# BM22192DA06_SCH.net
KiCad netlist of a schematic drawn in Altium Designer
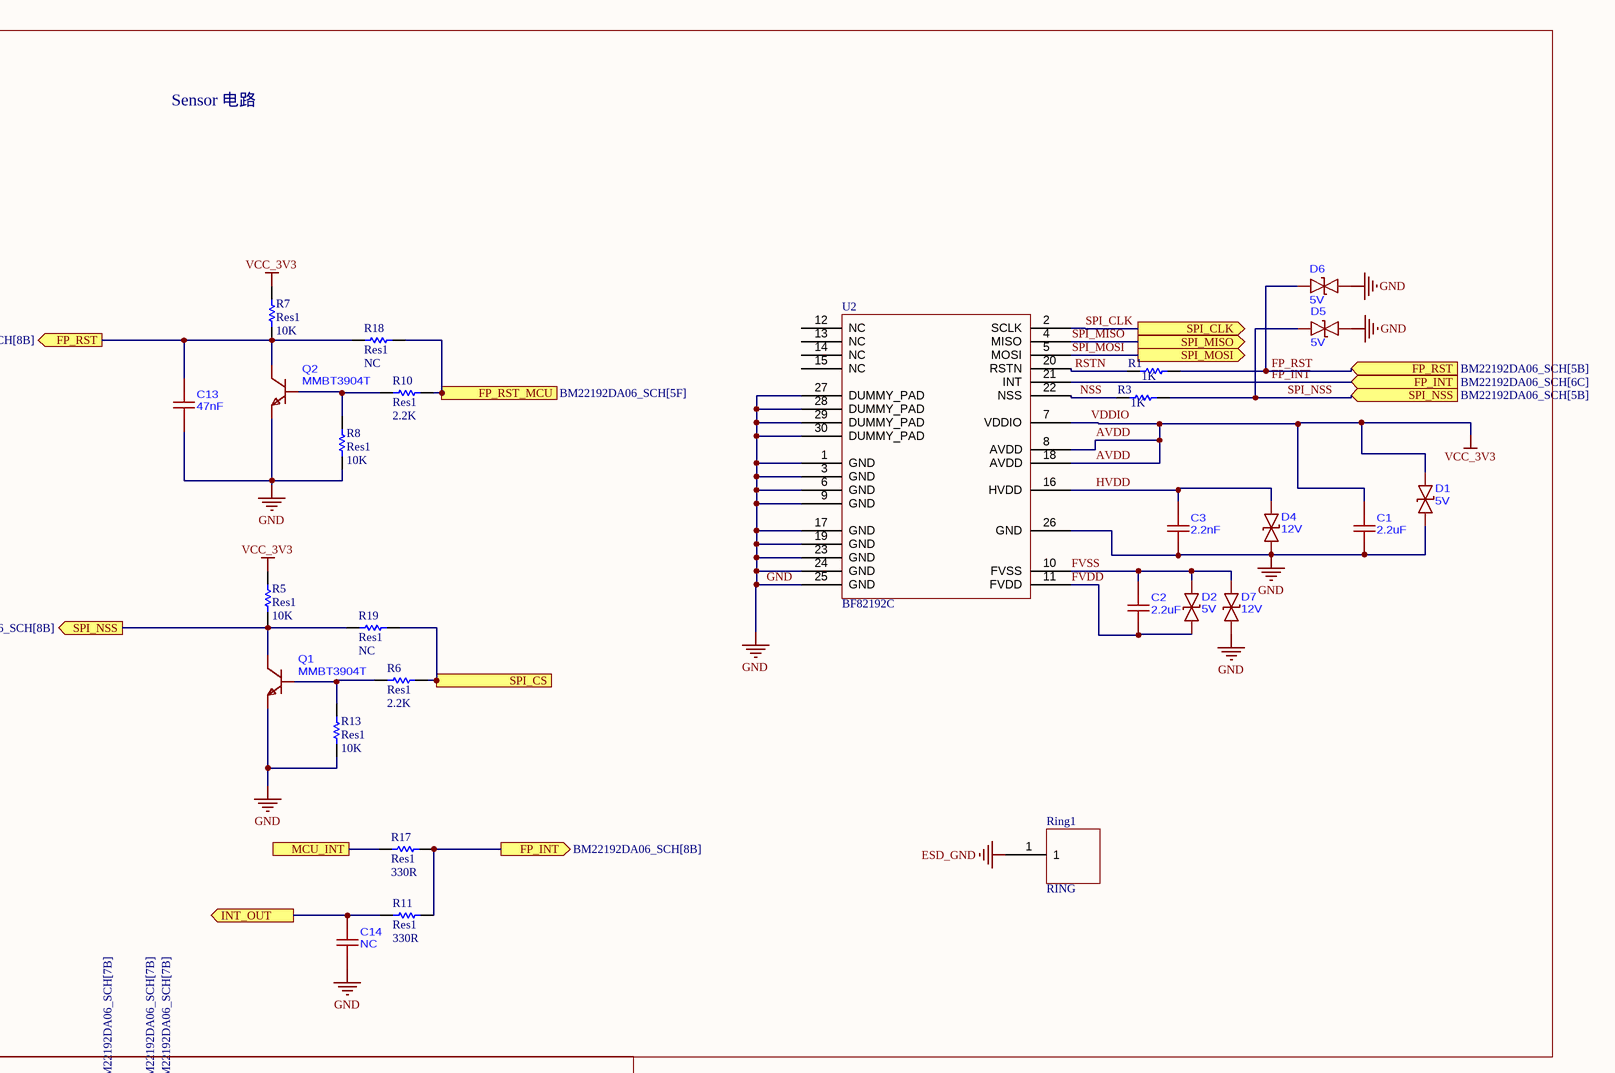
[diagram p0: BM22192DA06_SCH.SchDoc, top right]
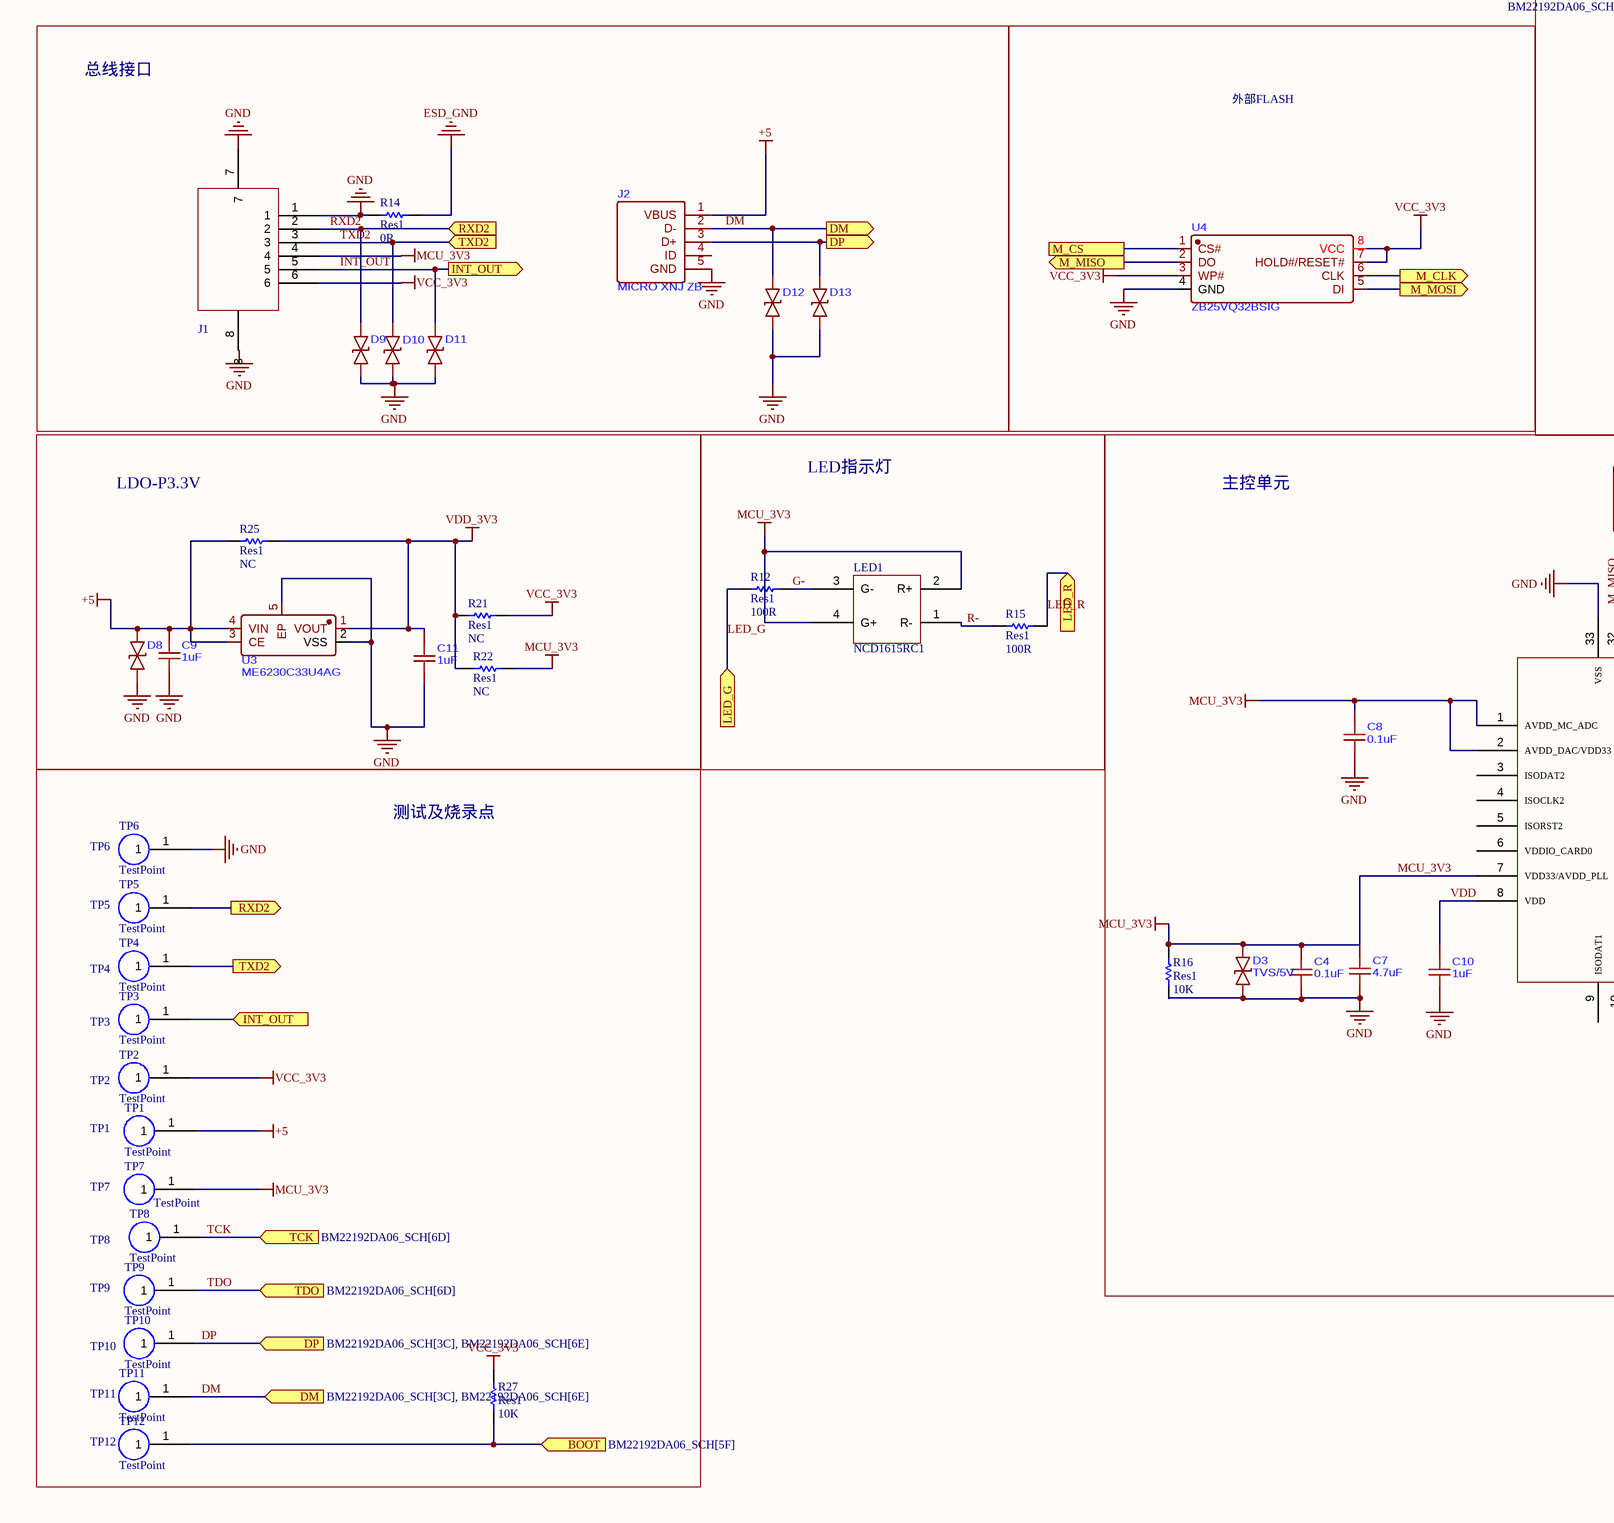
[diagram p1: BM22192DA06_SCH.SchDoc, bottom left]
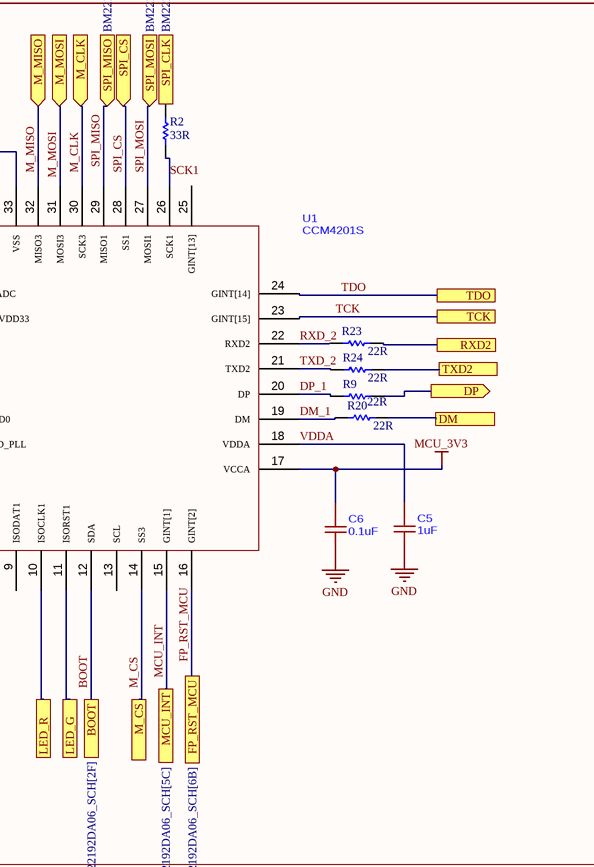
[diagram p2: BM22192DA06_SCH.SchDoc, bottom right]

(export (version "E")
  (design (tool "Eeschema 10.0.6"))
  (components
    (comp (ref "C1")
      (value "2.2uF")
      (footprint "C0201")
      (description "CAP")
      (libsource (lib "BLM") (part "C0201"))
    )
    (comp (ref "C2")
      (value "2.2uF")
      (footprint "C0201")
      (description "CAP")
      (libsource (lib "BLM") (part "C0201"))
    )
    (comp (ref "C3")
      (value "2.2nF")
      (footprint "C0201")
      (description "CAP")
      (libsource (lib "BLM") (part "C0201"))
    )
    (comp (ref "C4")
      (value "0.1uF")
      (footprint "C0201")
      (description "CAP")
      (libsource (lib "BLM") (part "C0201"))
    )
    (comp (ref "C5") (value "1uF") (footprint "C0402") (libsource (lib "BLM") (part "C0201")))
    (comp (ref "C6")
      (value "0.1uF")
      (footprint "C0201")
      (description "CAP")
      (libsource (lib "BLM") (part "C0201"))
    )
    (comp (ref "C7") (value "4.7uF") (footprint "C0402") (libsource (lib "BLM") (part "C0201")))
    (comp (ref "C8")
      (value "0.1uF")
      (footprint "C0201")
      (description "CAP")
      (libsource (lib "BLM") (part "C0201"))
    )
    (comp (ref "C9") (value "1uF") (footprint "C0402") (libsource (lib "BLM") (part "C0201")))
    (comp (ref "C10") (value "1uF") (footprint "C0402") (libsource (lib "BLM") (part "C0201")))
    (comp (ref "C11") (value "1uF") (footprint "C0402") (libsource (lib "BLM") (part "C0201")))
    (comp (ref "C13")
      (value "47nF")
      (footprint "C0201")
      (description "CAP")
      (libsource (lib "BLM") (part "C0201"))
    )
    (comp (ref "C14")
      (value "NC")
      (footprint "C0201")
      (description "CAP")
      (libsource (lib "BLM") (part "C0201"))
    )
    (comp (ref "D1")
      (value "5V")
      (footprint "D0201-BI_A")
      (description "TVS")
      (libsource (lib "BLM") (part "RSFK9D3NT"))
    )
    (comp (ref "D2")
      (value "5V")
      (footprint "D0201-BI_A")
      (description "TVS")
      (libsource (lib "BLM") (part "RSFK9D3NT"))
    )
    (comp (ref "D3")
      (value "TVS/5V")
      (footprint "D0201-BI_A")
      (description "TVS")
      (libsource (lib "BLM") (part "RSFK9D3NT"))
    )
    (comp (ref "D4")
      (value "12V")
      (footprint "D0201-BI_A")
      (description "TVS")
      (libsource (lib "BLM") (part "RSFK9D3NT"))
    )
    (comp (ref "D5")
      (value "5V")
      (footprint "D0201-BI_A")
      (description "TVS")
      (libsource (lib "BLM") (part "RSFK9D3NT"))
    )
    (comp (ref "D6")
      (value "5V")
      (footprint "D0201-BI_A")
      (description "TVS")
      (libsource (lib "BLM") (part "RSFK9D3NT"))
    )
    (comp (ref "D7")
      (value "12V")
      (footprint "D0201-BI_A")
      (description "TVS")
      (libsource (lib "BLM") (part "RSFK9D3NT"))
    )
    (comp (ref "D8")
      (value "RSFK9D3NT")
      (footprint "D0201-BI_A")
      (description "TVS")
      (libsource (lib "BLM") (part "RSFK9D3NT"))
    )
    (comp (ref "D9") (value "RSFK9D3NT") (footprint "D0201-BI_A") (libsource (lib "BLM") (part "RSFK9D3NT")))
    (comp (ref "D10") (value "RSFK9D3NT") (footprint "D0201-BI_A") (libsource (lib "BLM") (part "RSFK9D3NT")))
    (comp (ref "D11") (value "RSFK9D3NT") (footprint "D0201-BI_A") (libsource (lib "BLM") (part "RSFK9D3NT")))
    (comp (ref "D12") (value "RSFK9D3NT") (footprint "D0201-BI_A") (libsource (lib "BLM") (part "RSFK9D3NT")))
    (comp (ref "D13") (value "RSFK9D3NT") (footprint "D0201-BI_A") (libsource (lib "BLM") (part "RSFK9D3NT")))
    (comp (ref "J1")
      (value "SM06B-GHS-TB(LF)(SN)")
      (footprint "CONN_SM06B-GHS-TB_JST")
      (description "Description")
      (libsource (lib "BLM") (part "SM06B-GHS-TBLFSN"))
    )
    (comp (ref "J2")
      (value "MICRO XNJ ZB")
      (footprint "MICRO-USB-SMD_MICRO-XNJ-ZB")
      (libsource (lib "BLM") (part "MICRO XNJ ZB"))
    )
    (comp (ref "LED1")
      (value "NCD1615RC1")
      (footprint "LED-SMD_4P-L1.6-W1.5-TL-1")
      (description "LED")
      (libsource (lib "BLM") (part "NCD1615RC1"))
    )
    (comp (ref "Q1")
      (value "MMBT3904T")
      (footprint "SOT-523-3_L1.6-W0.8-P1.00-LS1.6-BR")
      (description "NPN triode")
      (libsource (lib "BLM") (part "MMBT3904T"))
    )
    (comp (ref "Q2")
      (value "MMBT3904T")
      (footprint "SOT-523-3_L1.6-W0.8-P1.00-LS1.6-BR")
      (description "NPN triode")
      (libsource (lib "BLM") (part "MMBT3904T"))
    )
    (comp (ref "R1")
      (value "1K")
      (footprint "R0201")
      (description "Resistor")
      (fields (field (name "Comment") "Res1") (field (name "PUBLISHER") "Altium Limited"))
      (libsource (lib "Miscellaneous Devices") (part "Res1"))
    )
    (comp (ref "R2")
      (value "33R")
      (footprint "R0201")
      (description "Resistor")
      (fields (field (name "Comment") "Res1") (field (name "PUBLISHER") "Altium Limited"))
      (libsource (lib "Miscellaneous Devices") (part "Res1"))
    )
    (comp (ref "R3")
      (value "1K")
      (footprint "R0201")
      (description "Resistor")
      (fields (field (name "Comment") "Res1") (field (name "PUBLISHER") "Altium Limited"))
      (libsource (lib "Miscellaneous Devices") (part "Res1"))
    )
    (comp (ref "R5")
      (value "Res1")
      (footprint "R0201")
      (description "Resistor")
      (fields (field (name "ALTIUM_VALUE") "10K") (field (name "PUBLISHER") "Altium Limited"))
      (libsource (lib "Miscellaneous Devices") (part "Res1"))
    )
    (comp (ref "R6")
      (value "Res1")
      (footprint "R0201")
      (description "Resistor")
      (fields (field (name "ALTIUM_VALUE") "2.2K") (field (name "PUBLISHER") "Altium Limited"))
      (libsource (lib "Miscellaneous Devices") (part "Res1"))
    )
    (comp (ref "R7")
      (value "Res1")
      (footprint "R0201")
      (description "Resistor")
      (fields (field (name "ALTIUM_VALUE") "10K") (field (name "PUBLISHER") "Altium Limited"))
      (libsource (lib "Miscellaneous Devices") (part "Res1"))
    )
    (comp (ref "R8")
      (value "Res1")
      (footprint "R0201")
      (description "Resistor")
      (fields (field (name "ALTIUM_VALUE") "10K") (field (name "PUBLISHER") "Altium Limited"))
      (libsource (lib "Miscellaneous Devices") (part "Res1"))
    )
    (comp (ref "R9")
      (value "22R")
      (footprint "R0201")
      (description "Resistor")
      (fields (field (name "Comment") "Res1") (field (name "PUBLISHER") "Altium Limited"))
      (libsource (lib "Miscellaneous Devices") (part "Res1"))
    )
    (comp (ref "R10")
      (value "Res1")
      (footprint "R0201")
      (description "Resistor")
      (fields (field (name "ALTIUM_VALUE") "2.2K") (field (name "PUBLISHER") "Altium Limited"))
      (libsource (lib "Miscellaneous Devices") (part "Res1"))
    )
    (comp (ref "R11")
      (value "Res1")
      (footprint "R0201")
      (description "Resistor")
      (fields (field (name "ALTIUM_VALUE") "330R") (field (name "PUBLISHER") "Altium Limited"))
      (libsource (lib "Miscellaneous Devices") (part "Res1"))
    )
    (comp (ref "R12")
      (value "Res1")
      (footprint "R0201")
      (description "Resistor")
      (fields (field (name "ALTIUM_VALUE") "100R") (field (name "PUBLISHER") "Altium Limited"))
      (libsource (lib "Miscellaneous Devices") (part "Res1"))
    )
    (comp (ref "R13")
      (value "Res1")
      (footprint "R0201")
      (description "Resistor")
      (fields (field (name "ALTIUM_VALUE") "10K") (field (name "PUBLISHER") "Altium Limited"))
      (libsource (lib "Miscellaneous Devices") (part "Res1"))
    )
    (comp (ref "R14")
      (value "Res1")
      (footprint "R0201")
      (description "Resistor")
      (fields (field (name "ALTIUM_VALUE") "0R") (field (name "PUBLISHER") "Altium Limited"))
      (libsource (lib "Miscellaneous Devices") (part "Res1"))
    )
    (comp (ref "R15")
      (value "Res1")
      (footprint "R0201")
      (description "Resistor")
      (fields (field (name "ALTIUM_VALUE") "100R") (field (name "PUBLISHER") "Altium Limited"))
      (libsource (lib "Miscellaneous Devices") (part "Res1"))
    )
    (comp (ref "R16")
      (value "Res1")
      (footprint "R0201")
      (description "Resistor")
      (fields (field (name "ALTIUM_VALUE") "10K") (field (name "PUBLISHER") "Altium Limited"))
      (libsource (lib "Miscellaneous Devices") (part "Res1"))
    )
    (comp (ref "R17")
      (value "Res1")
      (footprint "R0201")
      (description "Resistor")
      (fields (field (name "ALTIUM_VALUE") "330R") (field (name "PUBLISHER") "Altium Limited"))
      (libsource (lib "Miscellaneous Devices") (part "Res1"))
    )
    (comp (ref "R18")
      (value "Res1")
      (footprint "R0201")
      (description "Resistor")
      (fields (field (name "ALTIUM_VALUE") "NC") (field (name "PUBLISHER") "Altium Limited"))
      (libsource (lib "Miscellaneous Devices") (part "Res1"))
    )
    (comp (ref "R19")
      (value "Res1")
      (footprint "R0201")
      (description "Resistor")
      (fields (field (name "ALTIUM_VALUE") "NC") (field (name "PUBLISHER") "Altium Limited"))
      (libsource (lib "Miscellaneous Devices") (part "Res1"))
    )
    (comp (ref "R20")
      (value "22R")
      (footprint "R0201")
      (description "Resistor")
      (fields (field (name "Comment") "Res1") (field (name "PUBLISHER") "Altium Limited"))
      (libsource (lib "Miscellaneous Devices") (part "Res1"))
    )
    (comp (ref "R21")
      (value "Res1")
      (footprint "R0201")
      (description "Resistor")
      (fields (field (name "ALTIUM_VALUE") "NC") (field (name "PUBLISHER") "Altium Limited"))
      (libsource (lib "Miscellaneous Devices") (part "Res1"))
    )
    (comp (ref "R22")
      (value "Res1")
      (footprint "R0201")
      (description "Resistor")
      (fields (field (name "ALTIUM_VALUE") "NC") (field (name "PUBLISHER") "Altium Limited"))
      (libsource (lib "Miscellaneous Devices") (part "Res1"))
    )
    (comp (ref "R23")
      (value "22R")
      (footprint "R0201")
      (description "Resistor")
      (fields (field (name "Comment") "Res1") (field (name "PUBLISHER") "Altium Limited"))
      (libsource (lib "Miscellaneous Devices") (part "Res1"))
    )
    (comp (ref "R24")
      (value "22R")
      (footprint "R0201")
      (description "Resistor")
      (fields (field (name "Comment") "Res1") (field (name "PUBLISHER") "Altium Limited"))
      (libsource (lib "Miscellaneous Devices") (part "Res1"))
    )
    (comp (ref "R25")
      (value "Res1")
      (footprint "R0201")
      (description "Resistor")
      (fields (field (name "ALTIUM_VALUE") "NC") (field (name "PUBLISHER") "Altium Limited"))
      (libsource (lib "Miscellaneous Devices") (part "Res1"))
    )
    (comp (ref "R27")
      (value "Res1")
      (footprint "R0201")
      (description "Resistor")
      (fields (field (name "ALTIUM_VALUE") "10K") (field (name "PUBLISHER") "Altium Limited"))
      (libsource (lib "Miscellaneous Devices") (part "Res1"))
    )
    (comp (ref "Ring1")
      (value "RING")
      (footprint "金属环")
      (description "Metal Ring")
      (libsource (lib "BLM") (part "RING"))
    )
    (comp (ref "TP1") (value "TestPoint") (footprint "TestPoint") (libsource (lib "BLM") (part "TestPoint")))
    (comp (ref "TP2") (value "TestPoint") (footprint "TestPoint") (libsource (lib "BLM") (part "TestPoint")))
    (comp (ref "TP3") (value "TestPoint") (footprint "TestPoint") (libsource (lib "BLM") (part "TestPoint")))
    (comp (ref "TP4") (value "TestPoint") (footprint "TestPoint") (libsource (lib "BLM") (part "TestPoint")))
    (comp (ref "TP5") (value "TestPoint") (footprint "TestPoint") (libsource (lib "BLM") (part "TestPoint")))
    (comp (ref "TP6") (value "TestPoint") (footprint "TestPoint") (libsource (lib "BLM") (part "TestPoint")))
    (comp (ref "TP7") (value "TestPoint") (footprint "TestPoint") (libsource (lib "BLM") (part "TestPoint")))
    (comp (ref "TP8") (value "TestPoint") (footprint "TestPoint") (libsource (lib "BLM") (part "TestPoint")))
    (comp (ref "TP9") (value "TestPoint") (footprint "TestPoint") (libsource (lib "BLM") (part "TestPoint")))
    (comp (ref "TP10") (value "TestPoint") (footprint "TestPoint") (libsource (lib "BLM") (part "TestPoint")))
    (comp (ref "TP11") (value "TestPoint") (footprint "TestPoint") (libsource (lib "BLM") (part "TestPoint")))
    (comp (ref "TP12") (value "TestPoint") (footprint "TestPoint") (libsource (lib "BLM") (part "TestPoint")))
    (comp (ref "U1")
      (value "CCM4201S")
      (footprint "QFN40P400X400X85_HS-33N")
      (libsource (lib "BLM") (part "CCM4201S"))
    )
    (comp (ref "U2") (value "BF82192C") (footprint "BF82192c") (libsource (lib "BLM") (part "BF82192C")))
    (comp (ref "U3")
      (value "ME6230C33U4AG")
      (footprint "FBP4L_L1.0-W1.0-P0.65-BL-EP")
      (description "LDO")
      (libsource (lib "BLM") (part "ME6230C33U4AG"))
    )
    (comp (ref "U4")
      (value "ZB25VQ32BSIG")
      (footprint "SOIJ-8_L5.3-W5.3-P1.27-LS7.9-BL")
      (libsource (lib "BLM") (part "ZB25VQ32BSIG"))
    )
  )
  (nets
    (net (code "1") (name "+5") (class "Default")
      (node (ref "C9") (pin "2") (pinfunction "2_2") (pintype "passive"))
      (node (ref "D8") (pin "2") (pinfunction "A_2") (pintype "passive"))
      (node (ref "J2") (pin "1") (pinfunction "VBUS_1") (pintype "passive"))
      (node (ref "R25") (pin "1") (pinfunction "1_1") (pintype "passive"))
      (node (ref "TP1") (pin "1") (pinfunction "1_1") (pintype "passive"))
      (node (ref "U3") (pin "3") (pinfunction "CE_3") (pintype "passive"))
      (node (ref "U3") (pin "4") (pinfunction "VIN_4") (pintype "passive"))
    )
    (net (code "2") (name "/BOOT") (class "Default")
      (node (ref "R27") (pin "1") (pinfunction "1_1") (pintype "passive"))
      (node (ref "TP12") (pin "1") (pinfunction "1_1") (pintype "passive"))
      (node (ref "U1") (pin "12") (pinfunction "SDA_12") (pintype "passive"))
    )
    (net (code "3") (name "/DM") (class "Default")
      (node (ref "D12") (pin "2") (pinfunction "A_2") (pintype "passive"))
      (node (ref "J2") (pin "2") (pinfunction "D-_2") (pintype "passive"))
      (node (ref "R20") (pin "1") (pinfunction "1_1") (pintype "passive"))
      (node (ref "TP11") (pin "1") (pinfunction "1_1") (pintype "passive"))
    )
    (net (code "4") (name "/DM_1") (class "Default")
      (node (ref "R20") (pin "2") (pinfunction "2_2") (pintype "passive"))
      (node (ref "U1") (pin "19") (pinfunction "DM_19") (pintype "passive"))
    )
    (net (code "5") (name "/DP") (class "Default")
      (node (ref "D13") (pin "2") (pinfunction "A_2") (pintype "passive"))
      (node (ref "J2") (pin "3") (pinfunction "D+_3") (pintype "passive"))
      (node (ref "R9") (pin "1") (pinfunction "1_1") (pintype "passive"))
      (node (ref "TP10") (pin "1") (pinfunction "1_1") (pintype "passive"))
    )
    (net (code "6") (name "/DP_1") (class "Default")
      (node (ref "R9") (pin "2") (pinfunction "2_2") (pintype "passive"))
      (node (ref "U1") (pin "20") (pinfunction "DP_20") (pintype "passive"))
    )
    (net (code "7") (name "/FP_INT") (class "Default")
      (node (ref "R11") (pin "2") (pinfunction "2_2") (pintype "passive"))
      (node (ref "R17") (pin "2") (pinfunction "2_2") (pintype "passive"))
      (node (ref "U2") (pin "21") (pinfunction "INT_21") (pintype "passive"))
    )
    (net (code "8") (name "/FP_RST") (class "Default")
      (node (ref "C13") (pin "2") (pinfunction "2_2") (pintype "passive"))
      (node (ref "D6") (pin "2") (pinfunction "A_2") (pintype "passive"))
      (node (ref "Q2") (pin "3") (pinfunction "C_3") (pintype "passive"))
      (node (ref "R1") (pin "2") (pinfunction "2_2") (pintype "passive"))
      (node (ref "R18") (pin "1") (pinfunction "1_1") (pintype "passive"))
      (node (ref "R7") (pin "2") (pinfunction "2_2") (pintype "passive"))
    )
    (net (code "9") (name "/FP_RST_MCU") (class "Default")
      (node (ref "R10") (pin "2") (pinfunction "2_2") (pintype "passive"))
      (node (ref "R18") (pin "2") (pinfunction "2_2") (pintype "passive"))
      (node (ref "U1") (pin "16") (pinfunction "GINT[2]_16") (pintype "passive"))
    )
    (net (code "10") (name "/FVDD") (class "Default")
      (node (ref "C2") (pin "1") (pinfunction "1_1") (pintype "passive"))
      (node (ref "D2") (pin "1") (pinfunction "K_1") (pintype "passive"))
      (node (ref "U2") (pin "11") (pinfunction "FVDD_11") (pintype "passive"))
    )
    (net (code "11") (name "/FVSS") (class "Default")
      (node (ref "C2") (pin "2") (pinfunction "2_2") (pintype "passive"))
      (node (ref "D2") (pin "2") (pinfunction "A_2") (pintype "passive"))
      (node (ref "D7") (pin "2") (pinfunction "A_2") (pintype "passive"))
      (node (ref "U2") (pin "10") (pinfunction "FVSS_10") (pintype "passive"))
    )
    (net (code "12") (name "/G-") (class "Default")
      (node (ref "LED1") (pin "3") (pinfunction "G-_3") (pintype "passive"))
      (node (ref "R12") (pin "2") (pinfunction "2_2") (pintype "passive"))
    )
    (net (code "13") (name "/HVDD") (class "Default")
      (node (ref "C3") (pin "2") (pinfunction "2_2") (pintype "passive"))
      (node (ref "D4") (pin "2") (pinfunction "A_2") (pintype "passive"))
      (node (ref "U2") (pin "16") (pinfunction "HVDD_16") (pintype "passive"))
    )
    (net (code "14") (name "/INT_OUT") (class "Default")
      (node (ref "C14") (pin "2") (pinfunction "2_2") (pintype "passive"))
      (node (ref "D11") (pin "1") (pinfunction "K_1") (pintype "passive"))
      (node (ref "J1") (pin "5") (pinfunction "5_5") (pintype "passive"))
      (node (ref "R11") (pin "1") (pinfunction "1_1") (pintype "passive"))
      (node (ref "TP3") (pin "1") (pinfunction "1_1") (pintype "passive"))
    )
    (net (code "15") (name "/LED_G") (class "Default")
      (node (ref "R12") (pin "1") (pinfunction "1_1") (pintype "passive"))
      (node (ref "U1") (pin "11") (pinfunction "ISORST1_11") (pintype "passive"))
    )
    (net (code "16") (name "/LED_R") (class "Default")
      (node (ref "R15") (pin "2") (pinfunction "2_2") (pintype "passive"))
      (node (ref "U1") (pin "10") (pinfunction "ISOCLK1_10") (pintype "passive"))
    )
    (net (code "17") (name "/MCU_INT") (class "Default")
      (node (ref "R17") (pin "1") (pinfunction "1_1") (pintype "passive"))
      (node (ref "U1") (pin "15") (pinfunction "GINT[1]_15") (pintype "passive"))
    )
    (net (code "18") (name "/M_CLK") (class "Default")
      (node (ref "U1") (pin "30") (pinfunction "SCK3_30") (pintype "passive"))
      (node (ref "U4") (pin "6") (pinfunction "CLK_6") (pintype "passive"))
    )
    (net (code "19") (name "/M_CS") (class "Default")
      (node (ref "U1") (pin "14") (pinfunction "SS3_14") (pintype "passive"))
      (node (ref "U4") (pin "1") (pinfunction "CS#_1") (pintype "passive"))
    )
    (net (code "20") (name "/M_MISO") (class "Default")
      (node (ref "U1") (pin "32") (pinfunction "MISO3_32") (pintype "passive"))
      (node (ref "U4") (pin "2") (pinfunction "DO_2") (pintype "passive"))
    )
    (net (code "21") (name "/M_MOSI") (class "Default")
      (node (ref "U1") (pin "31") (pinfunction "MOSI3_31") (pintype "passive"))
      (node (ref "U4") (pin "5") (pinfunction "DI_5") (pintype "passive"))
    )
    (net (code "22") (name "/NSS") (class "Default")
      (node (ref "R3") (pin "1") (pinfunction "1_1") (pintype "passive"))
      (node (ref "U2") (pin "22") (pinfunction "NSS_22") (pintype "passive"))
    )
    (net (code "23") (name "/R-") (class "Default")
      (node (ref "LED1") (pin "1") (pinfunction "R-_1") (pintype "passive"))
      (node (ref "R15") (pin "1") (pinfunction "1_1") (pintype "passive"))
    )
    (net (code "24") (name "/RSTN") (class "Default")
      (node (ref "R1") (pin "1") (pinfunction "1_1") (pintype "passive"))
      (node (ref "U2") (pin "20") (pinfunction "RSTN_20") (pintype "passive"))
    )
    (net (code "25") (name "/RXD2") (class "Default")
      (node (ref "D9") (pin "2") (pinfunction "A_2") (pintype "passive"))
      (node (ref "J1") (pin "2") (pinfunction "2_2") (pintype "passive"))
      (node (ref "R23") (pin "1") (pinfunction "1_1") (pintype "passive"))
      (node (ref "TP5") (pin "1") (pinfunction "1_1") (pintype "passive"))
    )
    (net (code "26") (name "/RXD_2") (class "Default")
      (node (ref "R23") (pin "2") (pinfunction "2_2") (pintype "passive"))
      (node (ref "U1") (pin "22") (pinfunction "RXD2_22") (pintype "passive"))
    )
    (net (code "27") (name "/SCK1") (class "Default")
      (node (ref "R2") (pin "2") (pinfunction "2_2") (pintype "passive"))
      (node (ref "U1") (pin "26") (pinfunction "SCK1_26") (pintype "passive"))
    )
    (net (code "28") (name "/SPI_CLK") (class "Default")
      (node (ref "R2") (pin "1") (pinfunction "1_1") (pintype "passive"))
      (node (ref "U2") (pin "2") (pinfunction "SCLK_2") (pintype "passive"))
    )
    (net (code "29") (name "/SPI_CS") (class "Default")
      (node (ref "R19") (pin "2") (pinfunction "2_2") (pintype "passive"))
      (node (ref "R6") (pin "2") (pinfunction "2_2") (pintype "passive"))
      (node (ref "U1") (pin "28") (pinfunction "SS1_28") (pintype "passive"))
    )
    (net (code "30") (name "/SPI_MISO") (class "Default")
      (node (ref "U1") (pin "29") (pinfunction "MISO1_29") (pintype "passive"))
      (node (ref "U2") (pin "4") (pinfunction "MISO_4") (pintype "passive"))
    )
    (net (code "31") (name "/SPI_MOSI") (class "Default")
      (node (ref "U1") (pin "27") (pinfunction "MOSI1_27") (pintype "passive"))
      (node (ref "U2") (pin "5") (pinfunction "MOSI_5") (pintype "passive"))
    )
    (net (code "32") (name "/SPI_NSS") (class "Default")
      (node (ref "D5") (pin "2") (pinfunction "A_2") (pintype "passive"))
      (node (ref "Q1") (pin "3") (pinfunction "C_3") (pintype "passive"))
      (node (ref "R19") (pin "1") (pinfunction "1_1") (pintype "passive"))
      (node (ref "R3") (pin "2") (pinfunction "2_2") (pintype "passive"))
      (node (ref "R5") (pin "2") (pinfunction "2_2") (pintype "passive"))
    )
    (net (code "33") (name "/TCK") (class "Default")
      (node (ref "TP8") (pin "1") (pinfunction "1_1") (pintype "passive"))
      (node (ref "U1") (pin "23") (pinfunction "GINT[15]_23") (pintype "passive"))
    )
    (net (code "34") (name "/TDO") (class "Default")
      (node (ref "TP9") (pin "1") (pinfunction "1_1") (pintype "passive"))
      (node (ref "U1") (pin "24") (pinfunction "GINT[14]_24") (pintype "passive"))
    )
    (net (code "35") (name "/TXD2") (class "Default")
      (node (ref "D10") (pin "1") (pinfunction "K_1") (pintype "passive"))
      (node (ref "J1") (pin "3") (pinfunction "3_3") (pintype "passive"))
      (node (ref "R24") (pin "1") (pinfunction "1_1") (pintype "passive"))
      (node (ref "TP4") (pin "1") (pinfunction "1_1") (pintype "passive"))
    )
    (net (code "36") (name "/TXD_2") (class "Default")
      (node (ref "R24") (pin "2") (pinfunction "2_2") (pintype "passive"))
      (node (ref "U1") (pin "21") (pinfunction "TXD2_21") (pintype "passive"))
    )
    (net (code "37") (name "/VDD") (class "Default")
      (node (ref "C10") (pin "2") (pinfunction "2_2") (pintype "passive"))
      (node (ref "U1") (pin "8") (pinfunction "VDD_8") (pintype "passive"))
    )
    (net (code "38") (name "/VDDA") (class "Default")
      (node (ref "C5") (pin "2") (pinfunction "2_2") (pintype "passive"))
      (node (ref "U1") (pin "18") (pinfunction "VDDA_18") (pintype "passive"))
    )
    (net (code "39") (name "ESD_GND") (class "Default")
      (node (ref "R14") (pin "2") (pinfunction "2_2") (pintype "passive"))
      (node (ref "Ring1") (pin "1") (pinfunction "1_1") (pintype "passive"))
    )
    (net (code "40") (name "GND") (class "Default")
      (node (ref "C1") (pin "1") (pinfunction "1_1") (pintype "passive"))
      (node (ref "C10") (pin "1") (pinfunction "1_1") (pintype "passive"))
      (node (ref "C11") (pin "1") (pinfunction "1_1") (pintype "passive"))
      (node (ref "C13") (pin "1") (pinfunction "1_1") (pintype "passive"))
      (node (ref "C14") (pin "1") (pinfunction "1_1") (pintype "passive"))
      (node (ref "C3") (pin "1") (pinfunction "1_1") (pintype "passive"))
      (node (ref "C4") (pin "1") (pinfunction "1_1") (pintype "passive"))
      (node (ref "C5") (pin "1") (pinfunction "1_1") (pintype "passive"))
      (node (ref "C6") (pin "1") (pinfunction "1_1") (pintype "passive"))
      (node (ref "C7") (pin "1") (pinfunction "1_1") (pintype "passive"))
      (node (ref "C8") (pin "1") (pinfunction "1_1") (pintype "passive"))
      (node (ref "C9") (pin "1") (pinfunction "1_1") (pintype "passive"))
      (node (ref "D1") (pin "2") (pinfunction "A_2") (pintype "passive"))
      (node (ref "D10") (pin "2") (pinfunction "A_2") (pintype "passive"))
      (node (ref "D11") (pin "2") (pinfunction "A_2") (pintype "passive"))
      (node (ref "D12") (pin "1") (pinfunction "K_1") (pintype "passive"))
      (node (ref "D13") (pin "1") (pinfunction "K_1") (pintype "passive"))
      (node (ref "D3") (pin "1") (pinfunction "K_1") (pintype "passive"))
      (node (ref "D4") (pin "1") (pinfunction "K_1") (pintype "passive"))
      (node (ref "D5") (pin "1") (pinfunction "K_1") (pintype "passive"))
      (node (ref "D6") (pin "1") (pinfunction "K_1") (pintype "passive"))
      (node (ref "D7") (pin "1") (pinfunction "K_1") (pintype "passive"))
      (node (ref "D8") (pin "1") (pinfunction "K_1") (pintype "passive"))
      (node (ref "D9") (pin "1") (pinfunction "K_1") (pintype "passive"))
      (node (ref "J1") (pin "1") (pinfunction "1_1") (pintype "passive"))
      (node (ref "J1") (pin "7") (pinfunction "7_7") (pintype "passive"))
      (node (ref "J2") (pin "5") (pinfunction "GND_5") (pintype "passive"))
      (node (ref "Q1") (pin "2") (pinfunction "E_2") (pintype "passive"))
      (node (ref "Q2") (pin "2") (pinfunction "E_2") (pintype "passive"))
      (node (ref "R13") (pin "2") (pinfunction "2_2") (pintype "passive"))
      (node (ref "R14") (pin "1") (pinfunction "1_1") (pintype "passive"))
      (node (ref "R16") (pin "2") (pinfunction "2_2") (pintype "passive"))
      (node (ref "R8") (pin "2") (pinfunction "2_2") (pintype "passive"))
      (node (ref "TP6") (pin "1") (pinfunction "1_1") (pintype "passive"))
      (node (ref "U1") (pin "33") (pinfunction "VSS_33") (pintype "passive"))
      (node (ref "U2") (pin "1") (pinfunction "GND_1") (pintype "passive"))
      (node (ref "U2") (pin "17") (pinfunction "GND_17") (pintype "passive"))
      (node (ref "U2") (pin "19") (pinfunction "GND_19") (pintype "passive"))
      (node (ref "U2") (pin "23") (pinfunction "GND_23") (pintype "passive"))
      (node (ref "U2") (pin "24") (pinfunction "GND_24") (pintype "passive"))
      (node (ref "U2") (pin "25") (pinfunction "GND_25") (pintype "passive"))
      (node (ref "U2") (pin "26") (pinfunction "GND_26") (pintype "passive"))
      (node (ref "U2") (pin "27") (pinfunction "DUMMY_PAD_27") (pintype "passive"))
      (node (ref "U2") (pin "28") (pinfunction "DUMMY_PAD_28") (pintype "passive"))
      (node (ref "U2") (pin "29") (pinfunction "DUMMY_PAD_29") (pintype "passive"))
      (node (ref "U2") (pin "3") (pinfunction "GND_3") (pintype "passive"))
      (node (ref "U2") (pin "30") (pinfunction "DUMMY_PAD_30") (pintype "passive"))
      (node (ref "U2") (pin "6") (pinfunction "GND_6") (pintype "passive"))
      (node (ref "U2") (pin "9") (pinfunction "GND_9") (pintype "passive"))
      (node (ref "U3") (pin "2") (pinfunction "VSS_2") (pintype "passive"))
      (node (ref "U3") (pin "5") (pinfunction "EP_5") (pintype "passive"))
      (node (ref "U4") (pin "4") (pinfunction "GND_4") (pintype "passive"))
    )
    (net (code "41") (name "MCU_3V3") (class "Default")
      (node (ref "C4") (pin "2") (pinfunction "2_2") (pintype "passive"))
      (node (ref "C6") (pin "2") (pinfunction "2_2") (pintype "passive"))
      (node (ref "C7") (pin "2") (pinfunction "2_2") (pintype "passive"))
      (node (ref "C8") (pin "2") (pinfunction "2_2") (pintype "passive"))
      (node (ref "D3") (pin "2") (pinfunction "A_2") (pintype "passive"))
      (node (ref "J1") (pin "4") (pinfunction "4_4") (pintype "passive"))
      (node (ref "LED1") (pin "2") (pinfunction "R+_2") (pintype "passive"))
      (node (ref "LED1") (pin "4") (pinfunction "G+_4") (pintype "passive"))
      (node (ref "R16") (pin "1") (pinfunction "1_1") (pintype "passive"))
      (node (ref "R22") (pin "2") (pinfunction "2_2") (pintype "passive"))
      (node (ref "TP7") (pin "1") (pinfunction "1_1") (pintype "passive"))
      (node (ref "U1") (pin "1") (pinfunction "AVDD_MC_ADC_1") (pintype "passive"))
      (node (ref "U1") (pin "17") (pinfunction "VCCA_17") (pintype "passive"))
      (node (ref "U1") (pin "2") (pinfunction "AVDD_DAC/VDD33_2") (pintype "passive"))
      (node (ref "U1") (pin "7") (pinfunction "VDD33/AVDD_PLL_7") (pintype "passive"))
    )
    (net (code "42") (name "Net-(Q1-B)") (class "Default")
      (node (ref "Q1") (pin "1") (pinfunction "B_1") (pintype "passive"))
      (node (ref "R13") (pin "1") (pinfunction "1_1") (pintype "passive"))
      (node (ref "R6") (pin "1") (pinfunction "1_1") (pintype "passive"))
    )
    (net (code "43") (name "Net-(Q2-B)") (class "Default")
      (node (ref "Q2") (pin "1") (pinfunction "B_1") (pintype "passive"))
      (node (ref "R10") (pin "1") (pinfunction "1_1") (pintype "passive"))
      (node (ref "R8") (pin "1") (pinfunction "1_1") (pintype "passive"))
    )
    (net (code "44") (name "VCC_3V3") (class "Default")
      (node (ref "C1") (pin "2") (pinfunction "2_2") (pintype "passive"))
      (node (ref "D1") (pin "1") (pinfunction "K_1") (pintype "passive"))
      (node (ref "J1") (pin "6") (pinfunction "6_6") (pintype "passive"))
      (node (ref "R21") (pin "2") (pinfunction "2_2") (pintype "passive"))
      (node (ref "R27") (pin "2") (pinfunction "2_2") (pintype "passive"))
      (node (ref "R5") (pin "1") (pinfunction "1_1") (pintype "passive"))
      (node (ref "R7") (pin "1") (pinfunction "1_1") (pintype "passive"))
      (node (ref "TP2") (pin "1") (pinfunction "1_1") (pintype "passive"))
      (node (ref "U2") (pin "18") (pinfunction "AVDD_18") (pintype "passive"))
      (node (ref "U2") (pin "7") (pinfunction "VDDIO_7") (pintype "passive"))
      (node (ref "U2") (pin "8") (pinfunction "AVDD_8") (pintype "passive"))
      (node (ref "U4") (pin "3") (pinfunction "WP#_3") (pintype "passive"))
      (node (ref "U4") (pin "7") (pinfunction "HOLD#/RESET#_7") (pintype "passive"))
      (node (ref "U4") (pin "8") (pinfunction "VCC_8") (pintype "passive"))
    )
    (net (code "45") (name "VDD_3V3") (class "Default")
      (node (ref "C11") (pin "2") (pinfunction "2_2") (pintype "passive"))
      (node (ref "R21") (pin "1") (pinfunction "1_1") (pintype "passive"))
      (node (ref "R22") (pin "1") (pinfunction "1_1") (pintype "passive"))
      (node (ref "R25") (pin "2") (pinfunction "2_2") (pintype "passive"))
      (node (ref "U3") (pin "1") (pinfunction "VOUT_1") (pintype "passive"))
    )
    (net (code "46") (name "unconnected-(J1-Pad8)") (class "Default")
      (node (ref "J1") (pin "8") (pinfunction "8_8") (pintype "passive"))
    )
    (net (code "47") (name "unconnected-(J2-ID-Pad4)") (class "Default")
      (node (ref "J2") (pin "4") (pinfunction "ID_4") (pintype "passive"))
    )
    (net (code "48") (name "unconnected-(U1-GINT[13]-Pad25)") (class "Default")
      (node (ref "U1") (pin "25") (pinfunction "GINT[13]_25") (pintype "passive"))
    )
    (net (code "49") (name "unconnected-(U1-ISOCLK2-Pad4)") (class "Default")
      (node (ref "U1") (pin "4") (pinfunction "ISOCLK2_4") (pintype "passive"))
    )
    (net (code "50") (name "unconnected-(U1-ISODAT1-Pad9)") (class "Default")
      (node (ref "U1") (pin "9") (pinfunction "ISODAT1_9") (pintype "passive"))
    )
    (net (code "51") (name "unconnected-(U1-ISODAT2-Pad3)") (class "Default")
      (node (ref "U1") (pin "3") (pinfunction "ISODAT2_3") (pintype "passive"))
    )
    (net (code "52") (name "unconnected-(U1-ISORST2-Pad5)") (class "Default")
      (node (ref "U1") (pin "5") (pinfunction "ISORST2_5") (pintype "passive"))
    )
    (net (code "53") (name "unconnected-(U1-SCL-Pad13)") (class "Default")
      (node (ref "U1") (pin "13") (pinfunction "SCL_13") (pintype "passive"))
    )
    (net (code "54") (name "unconnected-(U1-VDDIO_CARD0-Pad6)") (class "Default")
      (node (ref "U1") (pin "6") (pinfunction "VDDIO_CARD0_6") (pintype "passive"))
    )
    (net (code "55") (name "unconnected-(U2-NC-Pad12)") (class "Default")
      (node (ref "U2") (pin "12") (pinfunction "NC_12") (pintype "passive"))
    )
    (net (code "56") (name "unconnected-(U2-NC-Pad13)") (class "Default")
      (node (ref "U2") (pin "13") (pinfunction "NC_13") (pintype "passive"))
    )
    (net (code "57") (name "unconnected-(U2-NC-Pad14)") (class "Default")
      (node (ref "U2") (pin "14") (pinfunction "NC_14") (pintype "passive"))
    )
    (net (code "58") (name "unconnected-(U2-NC-Pad15)") (class "Default")
      (node (ref "U2") (pin "15") (pinfunction "NC_15") (pintype "passive"))
    )
  )
)
